# Power.net
KiCad netlist of a schematic drawn in Altium Designer
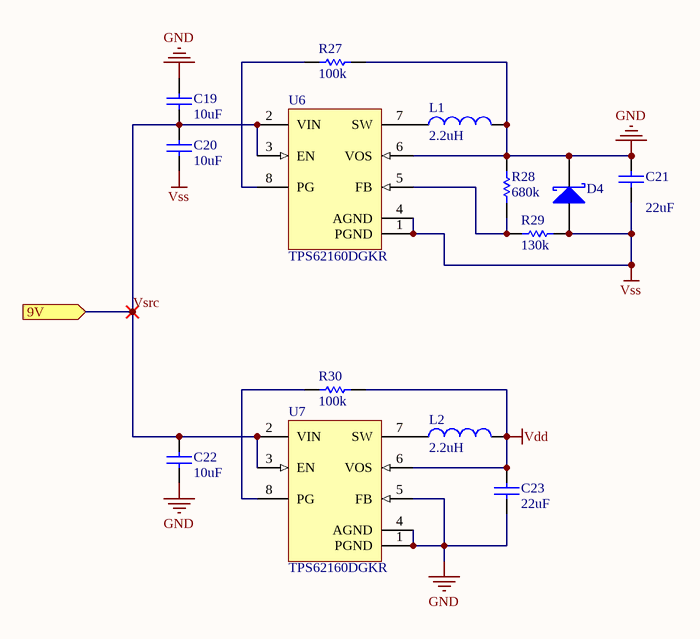
[diagram p0: Power.SchDoc]

(export (version "E")
  (design (tool "Eeschema 10.0.6"))
  (components
    (comp (ref "C19")
      (value "10uF")
      (footprint "C1206")
      (description "Capacitor")
      (fields (field (name "Comment") "Cap") (field (name "PUBLISHER") "Altium Limited"))
      (libsource (lib "Miscellaneous Devices") (part "Cap"))
    )
    (comp (ref "C20")
      (value "10uF")
      (footprint "C1206")
      (description "Capacitor")
      (fields (field (name "Comment") "Cap") (field (name "PUBLISHER") "Altium Limited"))
      (libsource (lib "Miscellaneous Devices") (part "Cap"))
    )
    (comp (ref "C21")
      (value "22uF")
      (footprint "C1206")
      (description "Capacitor")
      (fields (field (name "Comment") "Cap") (field (name "PUBLISHER") "Altium Limited"))
      (libsource (lib "Miscellaneous Devices") (part "Cap"))
    )
    (comp (ref "C22")
      (value "10uF")
      (footprint "C1206")
      (description "Capacitor")
      (fields (field (name "Comment") "Cap") (field (name "PUBLISHER") "Altium Limited"))
      (libsource (lib "Miscellaneous Devices") (part "Cap"))
    )
    (comp (ref "C23")
      (value "22uF")
      (footprint "C1206")
      (description "Capacitor")
      (fields (field (name "Comment") "Cap") (field (name "PUBLISHER") "Altium Limited"))
      (libsource (lib "Miscellaneous Devices") (part "Cap"))
    )
    (comp (ref "D4")
      (value "D Schottky")
      (footprint "425")
      (description "Schottky Diode")
      (fields (field (name "PUBLISHER") "Altium Limited"))
      (libsource (lib "Miscellaneous Devices") (part "D Schottky"))
    )
    (comp (ref "L1")
      (value "2.2uH")
      (footprint "1608[0603]")
      (description "Inductor")
      (fields (field (name "PUBLISHER") "Altium Limited"))
      (libsource (lib "Miscellaneous Devices") (part "Inductor"))
    )
    (comp (ref "L2")
      (value "2.2uH")
      (footprint "1608[0603]")
      (description "Inductor")
      (fields (field (name "PUBLISHER") "Altium Limited"))
      (libsource (lib "Miscellaneous Devices") (part "Inductor"))
    )
    (comp (ref "R27")
      (value "100k")
      (footprint "C1206")
      (description "Resistor")
      (fields (field (name "Comment") "Res1") (field (name "PUBLISHER") "Altium Limited"))
      (libsource (lib "Miscellaneous Devices") (part "Res1"))
    )
    (comp (ref "R28")
      (value "680k")
      (footprint "C1206")
      (description "Resistor")
      (fields (field (name "Comment") "Res1") (field (name "PUBLISHER") "Altium Limited"))
      (libsource (lib "Miscellaneous Devices") (part "Res1"))
    )
    (comp (ref "R29")
      (value "130k")
      (footprint "C1206")
      (description "Resistor")
      (fields (field (name "Comment") "Res1") (field (name "PUBLISHER") "Altium Limited"))
      (libsource (lib "Miscellaneous Devices") (part "Res1"))
    )
    (comp (ref "R30")
      (value "100k")
      (footprint "C1206")
      (description "Resistor")
      (fields (field (name "Comment") "Res1") (field (name "PUBLISHER") "Altium Limited"))
      (libsource (lib "Miscellaneous Devices") (part "Res1"))
    )
    (comp (ref "U6")
      (value "TPS62160DGKR")
      (footprint "DGK8_N")
      (fields (field (name "MANUFACTURER") "Texas Instruments"))
      (libsource (lib "TI Power Management Step-Down Regulator") (part "TPS62160DGKR"))
    )
    (comp (ref "U7")
      (value "TPS62160DGKR")
      (footprint "DGK8_N")
      (fields (field (name "MANUFACTURER") "Texas Instruments"))
      (libsource (lib "TI Power Management Step-Down Regulator") (part "TPS62160DGKR"))
    )
  )
  (nets
    (net (code "1") (name "/Vsrc") (class "Default")
      (node (ref "C19") (pin "1") (pinfunction "1_1") (pintype "passive"))
      (node (ref "C20") (pin "2") (pinfunction "2_2") (pintype "passive"))
      (node (ref "C22") (pin "2") (pinfunction "2_2") (pintype "passive"))
      (node (ref "U6") (pin "2") (pinfunction "VIN_2") (pintype "power_in"))
      (node (ref "U6") (pin "3") (pinfunction "EN_3") (pintype "input"))
      (node (ref "U7") (pin "2") (pinfunction "VIN_2") (pintype "power_in"))
      (node (ref "U7") (pin "3") (pinfunction "EN_3") (pintype "input"))
    )
    (net (code "2") (name "GND") (class "Default")
      (node (ref "C19") (pin "2") (pinfunction "2_2") (pintype "passive"))
      (node (ref "C21") (pin "2") (pinfunction "2_2") (pintype "passive"))
      (node (ref "C22") (pin "1") (pinfunction "1_1") (pintype "passive"))
      (node (ref "C23") (pin "1") (pinfunction "1_1") (pintype "passive"))
      (node (ref "D4") (pin "2") (pinfunction "K_2") (pintype "passive"))
      (node (ref "L1") (pin "2") (pinfunction "2_2") (pintype "passive"))
      (node (ref "R27") (pin "2") (pinfunction "2_2") (pintype "passive"))
      (node (ref "R28") (pin "2") (pinfunction "2_2") (pintype "passive"))
      (node (ref "U6") (pin "6") (pinfunction "VOS_6") (pintype "input"))
      (node (ref "U7") (pin "1") (pinfunction "PGND_1") (pintype "power_in"))
      (node (ref "U7") (pin "4") (pinfunction "AGND_4") (pintype "power_in"))
      (node (ref "U7") (pin "5") (pinfunction "FB_5") (pintype "input"))
    )
    (net (code "3") (name "Net-(U6-FB)") (class "Default")
      (node (ref "R28") (pin "1") (pinfunction "1_1") (pintype "passive"))
      (node (ref "R29") (pin "1") (pinfunction "1_1") (pintype "passive"))
      (node (ref "U6") (pin "5") (pinfunction "FB_5") (pintype "input"))
    )
    (net (code "4") (name "Net-(U6-PG)") (class "Default")
      (node (ref "R27") (pin "1") (pinfunction "1_1") (pintype "passive"))
      (node (ref "U6") (pin "8") (pinfunction "PG_8") (pintype "tri_state"))
    )
    (net (code "5") (name "Net-(U6-SW)") (class "Default")
      (node (ref "L1") (pin "1") (pinfunction "1_1") (pintype "passive"))
      (node (ref "U6") (pin "7") (pinfunction "SW_7") (pintype "power_in"))
    )
    (net (code "6") (name "Net-(U7-PG)") (class "Default")
      (node (ref "R30") (pin "1") (pinfunction "1_1") (pintype "passive"))
      (node (ref "U7") (pin "8") (pinfunction "PG_8") (pintype "tri_state"))
    )
    (net (code "7") (name "Net-(U7-SW)") (class "Default")
      (node (ref "L2") (pin "1") (pinfunction "1_1") (pintype "passive"))
      (node (ref "U7") (pin "7") (pinfunction "SW_7") (pintype "power_in"))
    )
    (net (code "8") (name "Vdd") (class "Default")
      (node (ref "C23") (pin "2") (pinfunction "2_2") (pintype "passive"))
      (node (ref "L2") (pin "2") (pinfunction "2_2") (pintype "passive"))
      (node (ref "R30") (pin "2") (pinfunction "2_2") (pintype "passive"))
      (node (ref "U7") (pin "6") (pinfunction "VOS_6") (pintype "input"))
    )
    (net (code "9") (name "Vss") (class "Default")
      (node (ref "C20") (pin "1") (pinfunction "1_1") (pintype "passive"))
      (node (ref "C21") (pin "1") (pinfunction "1_1") (pintype "passive"))
      (node (ref "D4") (pin "1") (pinfunction "A_1") (pintype "passive"))
      (node (ref "R29") (pin "2") (pinfunction "2_2") (pintype "passive"))
      (node (ref "U6") (pin "1") (pinfunction "PGND_1") (pintype "power_in"))
      (node (ref "U6") (pin "4") (pinfunction "AGND_4") (pintype "power_in"))
    )
  )
)
